# main.net
KiCad netlist of a schematic drawn in Altium Designer
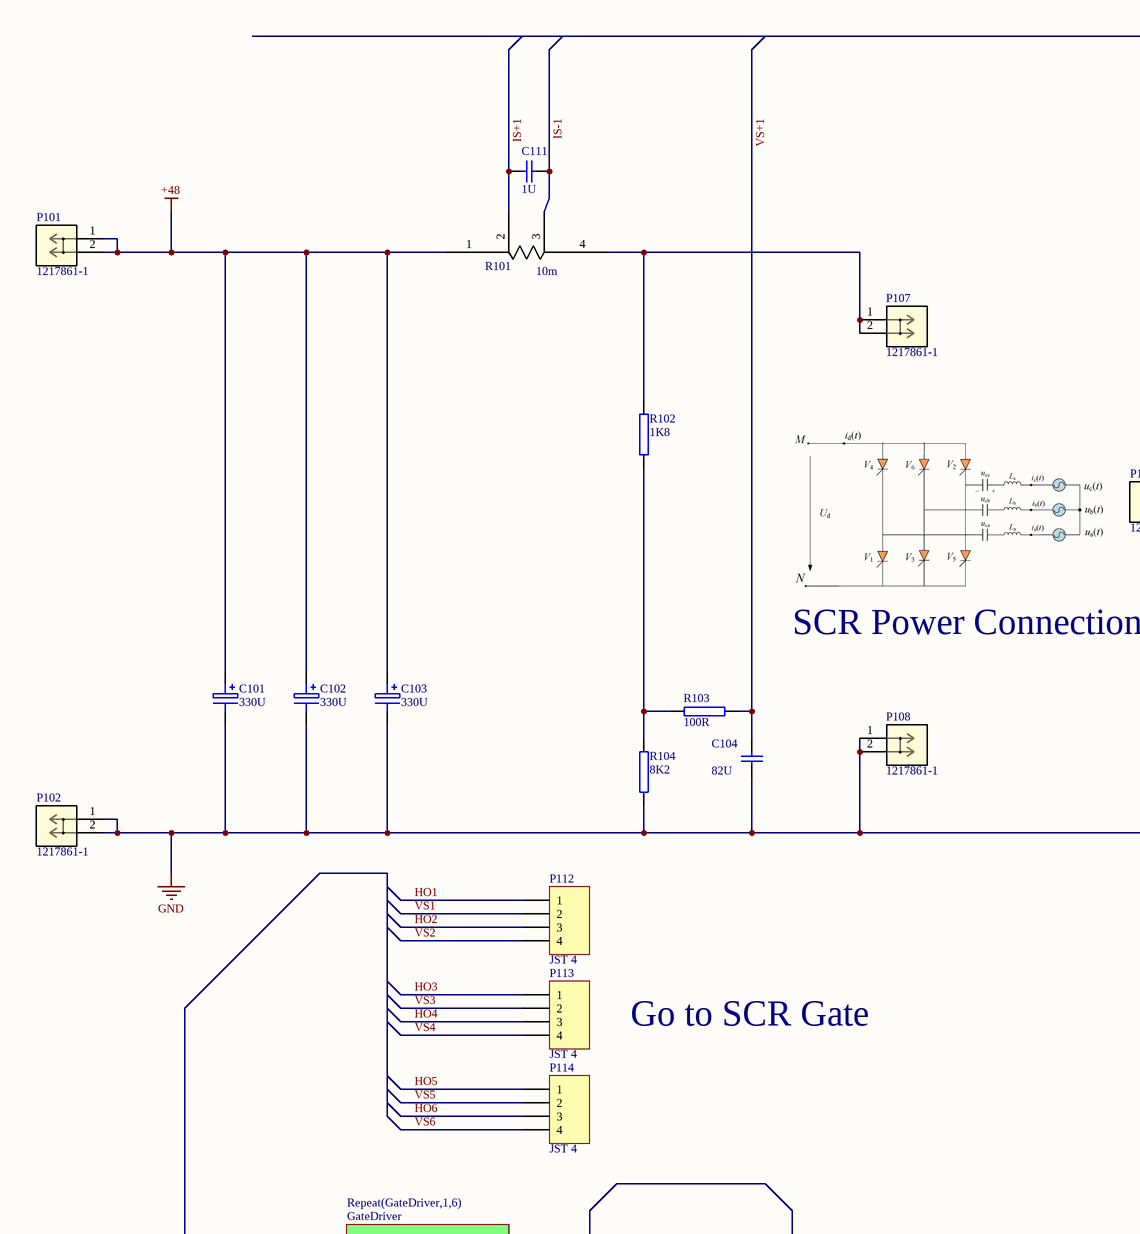
[diagram p0: main.SchDoc, top left]
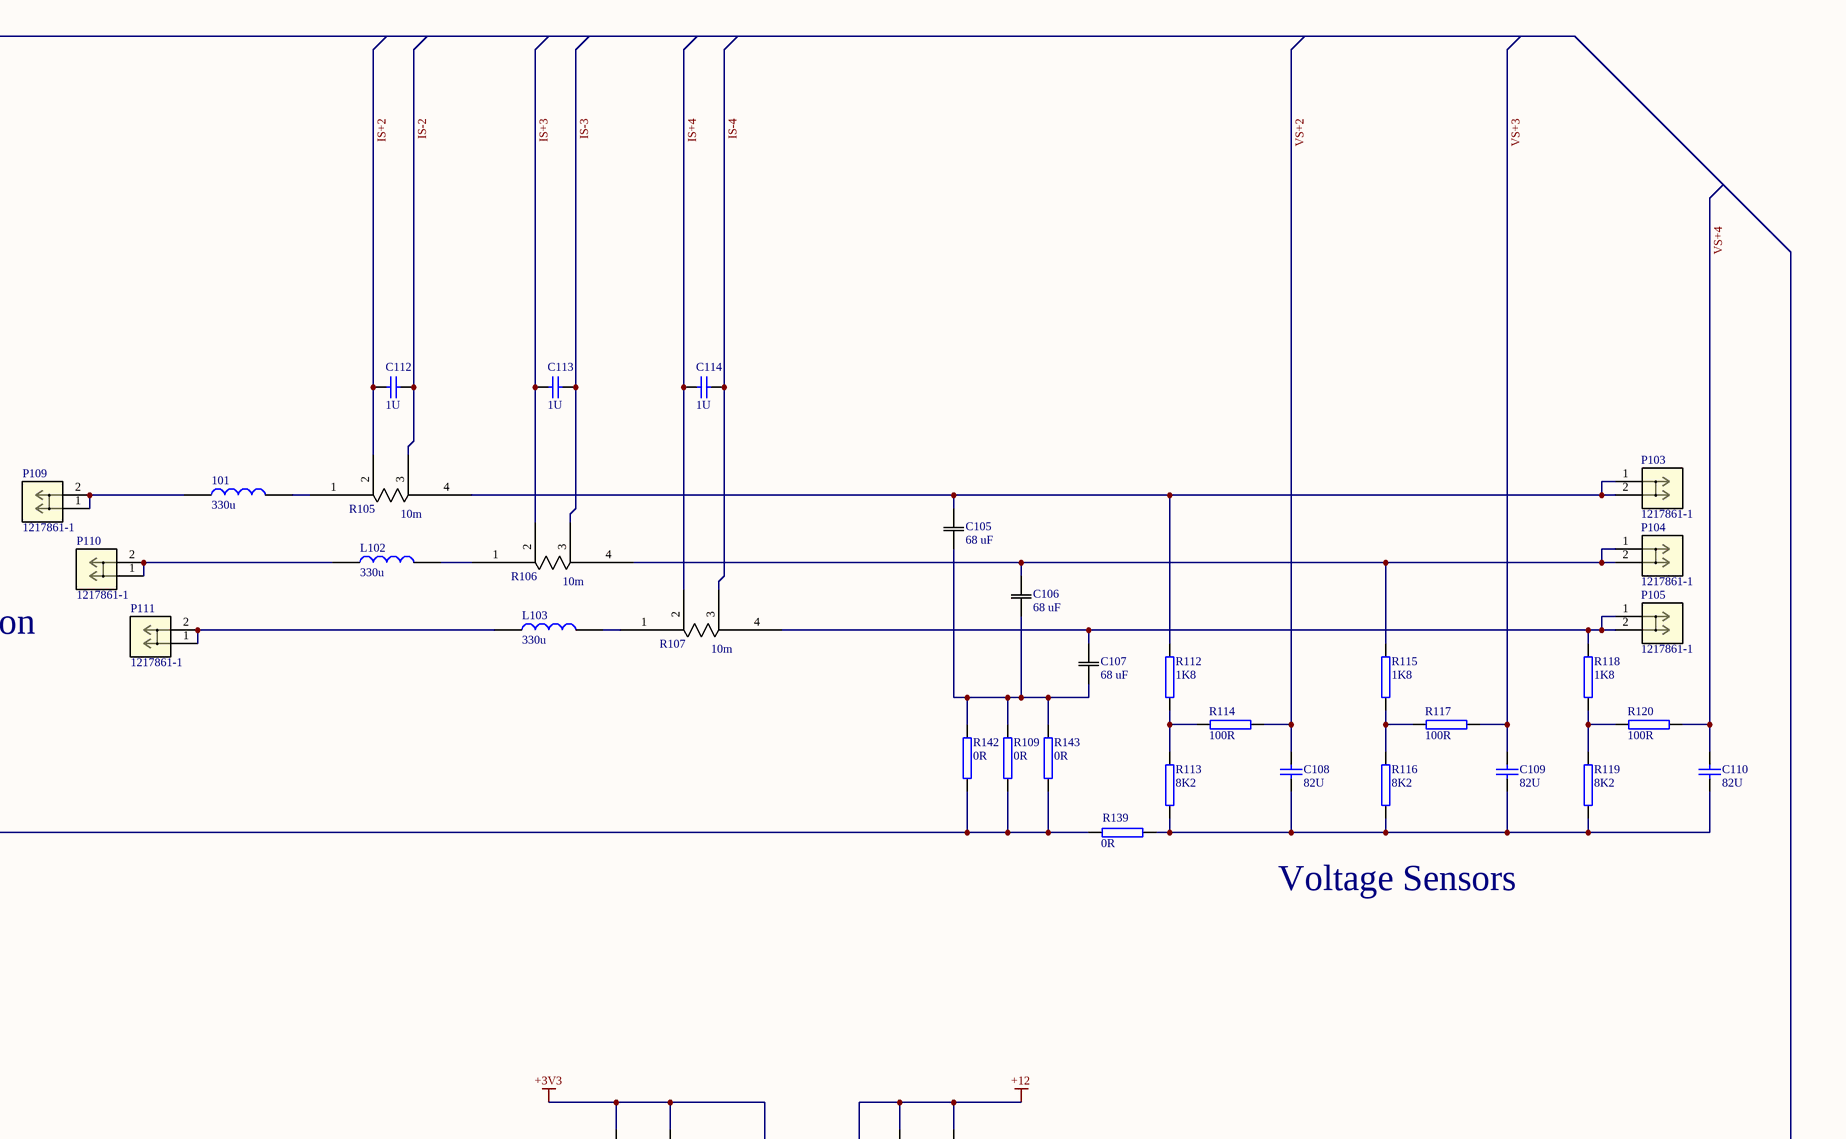
[diagram p1: main.SchDoc, top right]
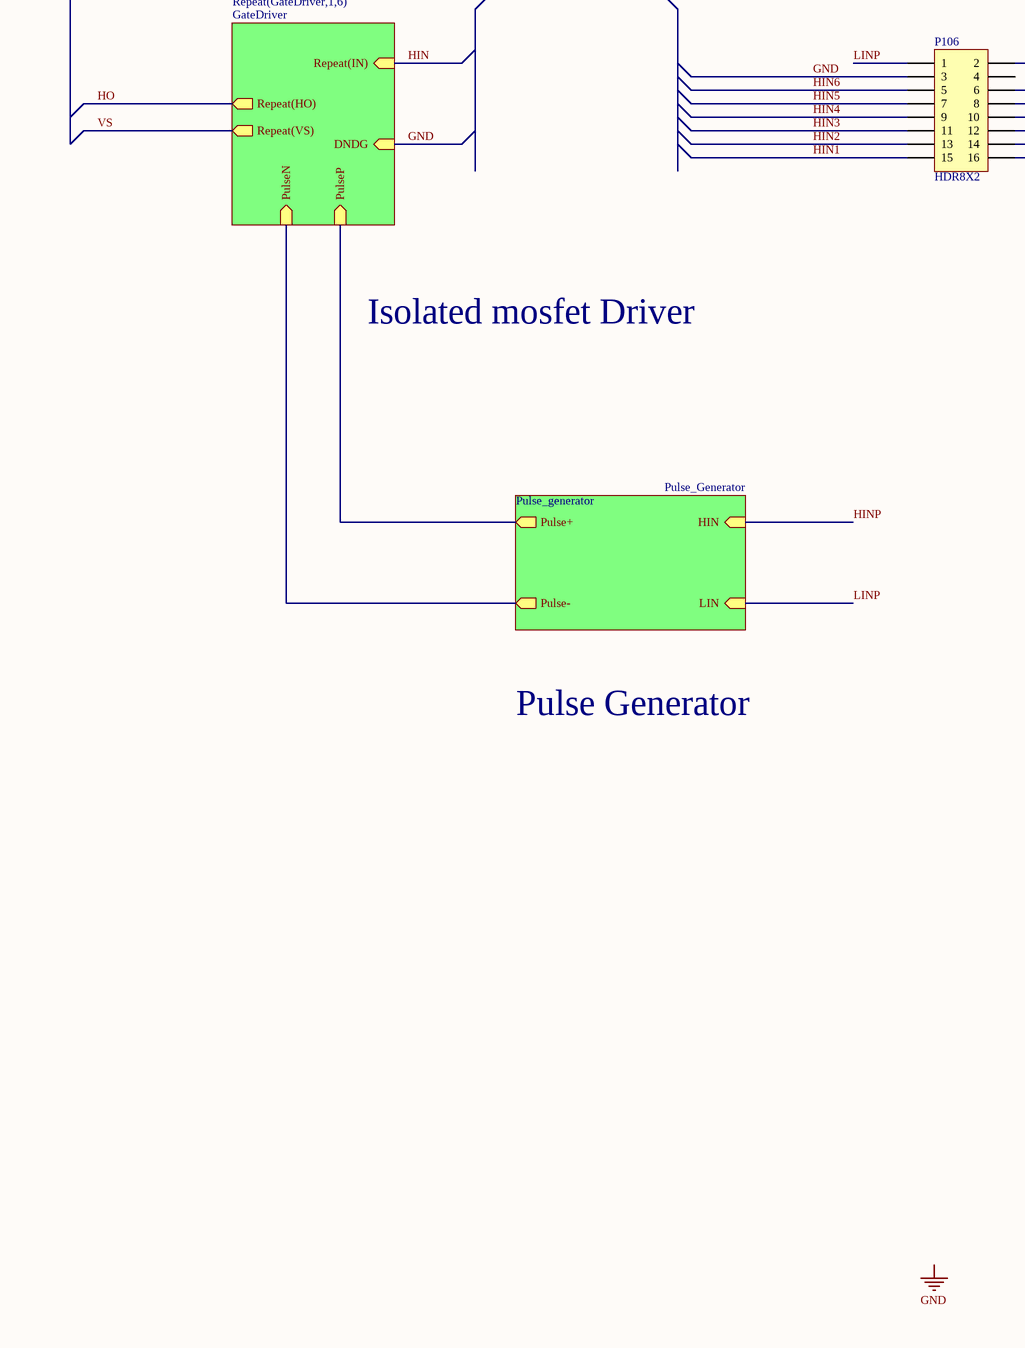
[diagram p2: main.SchDoc, bottom left]
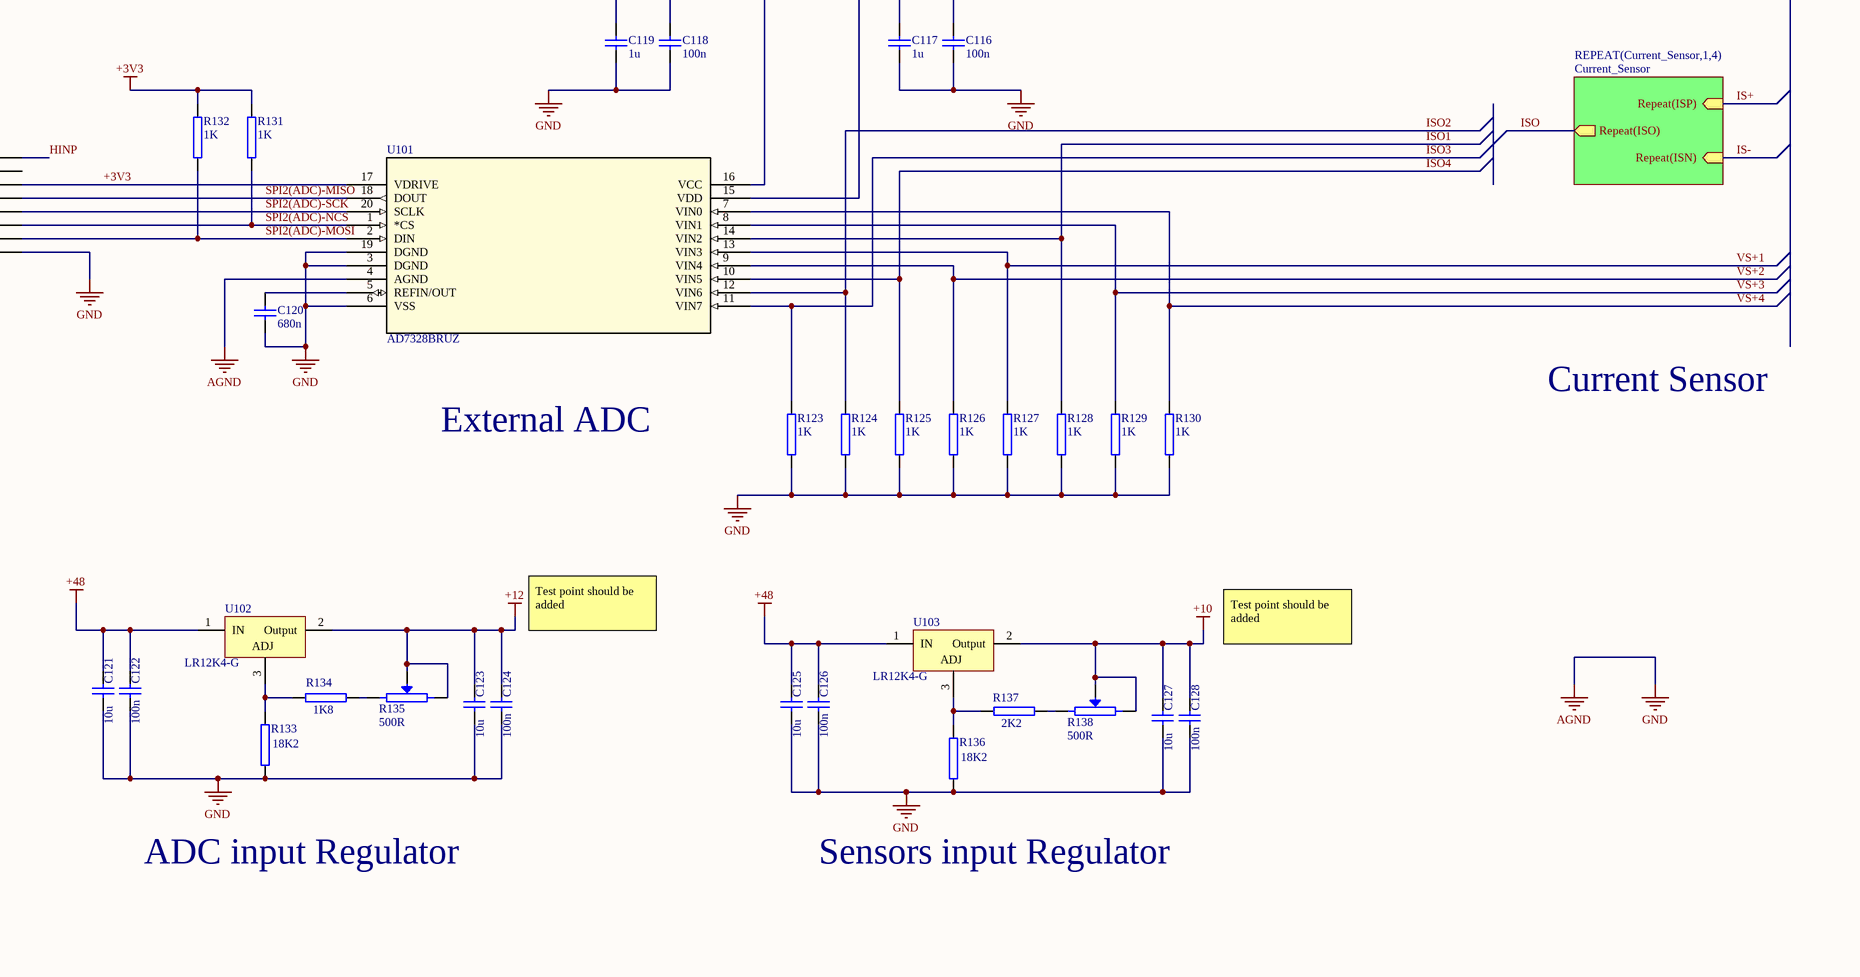
[diagram p3: main.SchDoc, bottom right]

(export (version "E")
  (design (tool "Eeschema 10.0.6"))
  (components
    (comp (ref "101")
      (value "330u")
      (footprint "1140-331K-RC")
      (libsource (lib "ENEL709_Schematic_Library") (part "1140-331K-RC"))
    )
    (comp (ref "C101")
      (value "330U")
      (footprint "CAPP300-600_AUT")
      (description "Polarized Aluminum Capacitor, Through Hole, Pitch 300mil, Body 600mil (Dia)")
      (libsource (lib "Resistors and Capacitors") (part "CAPP300-600"))
    )
    (comp (ref "C102")
      (value "330U")
      (footprint "CAPP300-600_AUT")
      (description "Polarized Aluminum Capacitor, Through Hole, Pitch 300mil, Body 600mil (Dia)")
      (libsource (lib "Resistors and Capacitors") (part "CAPP300-600"))
    )
    (comp (ref "C103")
      (value "330U")
      (footprint "CAPP300-600_AUT")
      (description "Polarized Aluminum Capacitor, Through Hole, Pitch 300mil, Body 600mil (Dia)")
      (libsource (lib "Resistors and Capacitors") (part "CAPP300-600"))
    )
    (comp (ref "C104")
      (value "82U")
      (footprint "CAP_1206")
      (description "Non Polarized Capacitor, SMD, 1206")
      (libsource (lib "Resistors and Capacitors") (part "CAPN 1206"))
    )
    (comp (ref "C105")
      (value "68 uF")
      (footprint "B32526R3686K000")
      (libsource (lib "ENEL709_Schematic_Library") (part "B32526R3686K000"))
    )
    (comp (ref "C106")
      (value "68 uF")
      (footprint "B32526R3686K000")
      (libsource (lib "ENEL709_Schematic_Library") (part "B32526R3686K000"))
    )
    (comp (ref "C107")
      (value "68 uF")
      (footprint "B32526R3686K000")
      (libsource (lib "ENEL709_Schematic_Library") (part "B32526R3686K000"))
    )
    (comp (ref "C108")
      (value "82U")
      (footprint "CAP_1206")
      (description "Non Polarized Capacitor, SMD, 1206")
      (libsource (lib "Resistors and Capacitors") (part "CAPN 1206"))
    )
    (comp (ref "C109")
      (value "82U")
      (footprint "CAP_1206")
      (description "Non Polarized Capacitor, SMD, 1206")
      (libsource (lib "Resistors and Capacitors") (part "CAPN 1206"))
    )
    (comp (ref "C110")
      (value "82U")
      (footprint "CAP_1206")
      (description "Non Polarized Capacitor, SMD, 1206")
      (libsource (lib "Resistors and Capacitors") (part "CAPN 1206"))
    )
    (comp (ref "C111")
      (value "1U")
      (footprint "CAP_1206")
      (description "Non Polarized Capacitor, SMD, 1206")
      (libsource (lib "Resistors and Capacitors") (part "CAPN 1206"))
    )
    (comp (ref "C112")
      (value "1U")
      (footprint "CAP_1206")
      (description "Non Polarized Capacitor, SMD, 1206")
      (libsource (lib "Resistors and Capacitors") (part "CAPN 1206"))
    )
    (comp (ref "C113")
      (value "1U")
      (footprint "CAP_1206")
      (description "Non Polarized Capacitor, SMD, 1206")
      (libsource (lib "Resistors and Capacitors") (part "CAPN 1206"))
    )
    (comp (ref "C114")
      (value "1U")
      (footprint "CAP_1206")
      (description "Non Polarized Capacitor, SMD, 1206")
      (libsource (lib "Resistors and Capacitors") (part "CAPN 1206"))
    )
    (comp (ref "C116")
      (value "100n")
      (footprint "CAP_1206")
      (description "Non Polarized Capacitor, SMD, 1206")
      (libsource (lib "Resistors and Capacitors") (part "CAPN 1206"))
    )
    (comp (ref "C117")
      (value "1u")
      (footprint "CAP_1206")
      (description "Non Polarized Capacitor, SMD, 1206")
      (libsource (lib "Resistors and Capacitors") (part "CAPN 1206"))
    )
    (comp (ref "C118")
      (value "100n")
      (footprint "CAP_1206")
      (description "Non Polarized Capacitor, SMD, 1206")
      (libsource (lib "Resistors and Capacitors") (part "CAPN 1206"))
    )
    (comp (ref "C119")
      (value "1u")
      (footprint "CAP_1206")
      (description "Non Polarized Capacitor, SMD, 1206")
      (libsource (lib "Resistors and Capacitors") (part "CAPN 1206"))
    )
    (comp (ref "C120")
      (value "680n")
      (footprint "CAP_1206")
      (description "Non Polarized Capacitor, SMD, 1206")
      (libsource (lib "Resistors and Capacitors") (part "CAPN 1206"))
    )
    (comp (ref "C121")
      (value "10u")
      (footprint "CAP_1206")
      (description "Non Polarized Capacitor, SMD, 1206")
      (libsource (lib "Resistors and Capacitors") (part "CAPN 1206"))
    )
    (comp (ref "C122")
      (value "100n")
      (footprint "CAP_1206")
      (description "Non Polarized Capacitor, SMD, 1206")
      (libsource (lib "Resistors and Capacitors") (part "CAPN 1206"))
    )
    (comp (ref "C123")
      (value "10u")
      (footprint "CAP_1206")
      (description "Non Polarized Capacitor, SMD, 1206")
      (libsource (lib "Resistors and Capacitors") (part "CAPN 1206"))
    )
    (comp (ref "C124")
      (value "100n")
      (footprint "CAP_1206")
      (description "Non Polarized Capacitor, SMD, 1206")
      (libsource (lib "Resistors and Capacitors") (part "CAPN 1206"))
    )
    (comp (ref "C125")
      (value "10u")
      (footprint "CAP_1206")
      (description "Non Polarized Capacitor, SMD, 1206")
      (libsource (lib "Resistors and Capacitors") (part "CAPN 1206"))
    )
    (comp (ref "C126")
      (value "100n")
      (footprint "CAP_1206")
      (description "Non Polarized Capacitor, SMD, 1206")
      (libsource (lib "Resistors and Capacitors") (part "CAPN 1206"))
    )
    (comp (ref "C127")
      (value "10u")
      (footprint "CAP_1206")
      (description "Non Polarized Capacitor, SMD, 1206")
      (libsource (lib "Resistors and Capacitors") (part "CAPN 1206"))
    )
    (comp (ref "C128")
      (value "100n")
      (footprint "CAP_1206")
      (description "Non Polarized Capacitor, SMD, 1206")
      (libsource (lib "Resistors and Capacitors") (part "CAPN 1206"))
    )
    (comp (ref "L102")
      (value "330u")
      (footprint "1140-331K-RC")
      (libsource (lib "ENEL709_Schematic_Library") (part "1140-331K-RC"))
    )
    (comp (ref "L103")
      (value "330u")
      (footprint "1140-331K-RC")
      (libsource (lib "ENEL709_Schematic_Library") (part "1140-331K-RC"))
    )
    (comp (ref "P101")
      (value "1217861-1")
      (footprint "CONN_1217861-1_TEC")
      (libsource (lib "") (part "1217861-1_2"))
    )
    (comp (ref "P102")
      (value "1217861-1")
      (footprint "CONN_1217861-1_TEC")
      (libsource (lib "") (part "1217861-1_2"))
    )
    (comp (ref "P103")
      (value "1217861-1")
      (footprint "CONN_1217861-1_TEC")
      (libsource (lib "Schlib") (part "1217861-1"))
    )
    (comp (ref "P104")
      (value "1217861-1")
      (footprint "CONN_1217861-1_TEC")
      (libsource (lib "Schlib") (part "1217861-1"))
    )
    (comp (ref "P105")
      (value "1217861-1")
      (footprint "CONN_1217861-1_TEC")
      (libsource (lib "Schlib") (part "1217861-1"))
    )
    (comp (ref "P106")
      (value "HDR8X2")
      (footprint "HDR2X8_AUT")
      (description "Header, 8-Pin, Dual row, 2.54mm Pitch, Straight")
      (libsource (lib "Connectors") (part "HDR8X2"))
    )
    (comp (ref "P107")
      (value "1217861-1")
      (footprint "CONN_1217861-1_TEC")
      (libsource (lib "Schlib") (part "1217861-1"))
    )
    (comp (ref "P108")
      (value "1217861-1")
      (footprint "CONN_1217861-1_TEC")
      (libsource (lib "Schlib") (part "1217861-1"))
    )
    (comp (ref "P109")
      (value "1217861-1")
      (footprint "CONN_1217861-1_TEC")
      (libsource (lib "") (part "1217861-1_1"))
    )
    (comp (ref "P110")
      (value "1217861-1")
      (footprint "CONN_1217861-1_TEC")
      (libsource (lib "") (part "1217861-1_1"))
    )
    (comp (ref "P111")
      (value "1217861-1")
      (footprint "CONN_1217861-1_TEC")
      (libsource (lib "") (part "1217861-1_1"))
    )
    (comp (ref "P112")
      (value "JST 4")
      (footprint "PA-4")
      (description "JST PA Header, 4-Pin, Pitch 2mm")
      (libsource (lib "Connectors") (part "JST PA Header 4"))
    )
    (comp (ref "P113")
      (value "JST 4")
      (footprint "PA-4")
      (description "JST PA Header, 4-Pin, Pitch 2mm")
      (libsource (lib "Connectors") (part "JST PA Header 4"))
    )
    (comp (ref "P114")
      (value "JST 4")
      (footprint "PA-4")
      (description "JST PA Header, 4-Pin, Pitch 2mm")
      (libsource (lib "Connectors") (part "JST PA Header 4"))
    )
    (comp (ref "R101")
      (value "10m")
      (footprint "WSL3673R_002-01")
      (description "Current Shunt \r\nKelvin 4W 0.002- 0.01")
      (libsource (lib "Projects_2025") (part "WSL3673R-01"))
    )
    (comp (ref "R102")
      (value "1K8")
      (footprint "RES_1206")
      (description "Resistor, SMD, 1206")
      (libsource (lib "Resistors and Capacitors") (part "Resistor 1206"))
    )
    (comp (ref "R103")
      (value "100R")
      (footprint "RES_1206")
      (description "Resistor, SMD, 1206")
      (libsource (lib "Resistors and Capacitors") (part "Resistor 1206"))
    )
    (comp (ref "R104")
      (value "8K2")
      (footprint "RES_1206")
      (description "Resistor, SMD, 1206")
      (libsource (lib "Resistors and Capacitors") (part "Resistor 1206"))
    )
    (comp (ref "R105")
      (value "10m")
      (footprint "WSL3673R_002-01")
      (description "Current Shunt \r\nKelvin 4W 0.002- 0.01")
      (libsource (lib "Projects_2025") (part "WSL3673R-01"))
    )
    (comp (ref "R106")
      (value "10m")
      (footprint "WSL3673R_002-01")
      (description "Current Shunt \r\nKelvin 4W 0.002- 0.01")
      (libsource (lib "Projects_2025") (part "WSL3673R-01"))
    )
    (comp (ref "R107")
      (value "10m")
      (footprint "WSL3673R_002-01")
      (description "Current Shunt \r\nKelvin 4W 0.002- 0.01")
      (libsource (lib "Projects_2025") (part "WSL3673R-01"))
    )
    (comp (ref "R109")
      (value "0R")
      (footprint "RES_1206")
      (description "Resistor, SMD, 1206")
      (libsource (lib "Resistors and Capacitors") (part "Resistor 1206"))
    )
    (comp (ref "R112")
      (value "1K8")
      (footprint "RES_1206")
      (description "Resistor, SMD, 1206")
      (libsource (lib "Resistors and Capacitors") (part "Resistor 1206"))
    )
    (comp (ref "R113")
      (value "8K2")
      (footprint "RES_1206")
      (description "Resistor, SMD, 1206")
      (libsource (lib "Resistors and Capacitors") (part "Resistor 1206"))
    )
    (comp (ref "R114")
      (value "100R")
      (footprint "RES_1206")
      (description "Resistor, SMD, 1206")
      (libsource (lib "Resistors and Capacitors") (part "Resistor 1206"))
    )
    (comp (ref "R115")
      (value "1K8")
      (footprint "RES_1206")
      (description "Resistor, SMD, 1206")
      (libsource (lib "Resistors and Capacitors") (part "Resistor 1206"))
    )
    (comp (ref "R116")
      (value "8K2")
      (footprint "RES_1206")
      (description "Resistor, SMD, 1206")
      (libsource (lib "Resistors and Capacitors") (part "Resistor 1206"))
    )
    (comp (ref "R117")
      (value "100R")
      (footprint "RES_1206")
      (description "Resistor, SMD, 1206")
      (libsource (lib "Resistors and Capacitors") (part "Resistor 1206"))
    )
    (comp (ref "R118")
      (value "1K8")
      (footprint "RES_1206")
      (description "Resistor, SMD, 1206")
      (libsource (lib "Resistors and Capacitors") (part "Resistor 1206"))
    )
    (comp (ref "R119")
      (value "8K2")
      (footprint "RES_1206")
      (description "Resistor, SMD, 1206")
      (libsource (lib "Resistors and Capacitors") (part "Resistor 1206"))
    )
    (comp (ref "R120")
      (value "100R")
      (footprint "RES_1206")
      (description "Resistor, SMD, 1206")
      (libsource (lib "Resistors and Capacitors") (part "Resistor 1206"))
    )
    (comp (ref "R123")
      (value "1K")
      (footprint "RES_1206")
      (description "Resistor, SMD, 1206")
      (libsource (lib "Resistors and Capacitors") (part "Resistor 1206"))
    )
    (comp (ref "R124")
      (value "1K")
      (footprint "RES_1206")
      (description "Resistor, SMD, 1206")
      (libsource (lib "Resistors and Capacitors") (part "Resistor 1206"))
    )
    (comp (ref "R125")
      (value "1K")
      (footprint "RES_1206")
      (description "Resistor, SMD, 1206")
      (libsource (lib "Resistors and Capacitors") (part "Resistor 1206"))
    )
    (comp (ref "R126")
      (value "1K")
      (footprint "RES_1206")
      (description "Resistor, SMD, 1206")
      (libsource (lib "Resistors and Capacitors") (part "Resistor 1206"))
    )
    (comp (ref "R127")
      (value "1K")
      (footprint "RES_1206")
      (description "Resistor, SMD, 1206")
      (libsource (lib "Resistors and Capacitors") (part "Resistor 1206"))
    )
    (comp (ref "R128")
      (value "1K")
      (footprint "RES_1206")
      (description "Resistor, SMD, 1206")
      (libsource (lib "Resistors and Capacitors") (part "Resistor 1206"))
    )
    (comp (ref "R129")
      (value "1K")
      (footprint "RES_1206")
      (description "Resistor, SMD, 1206")
      (libsource (lib "Resistors and Capacitors") (part "Resistor 1206"))
    )
    (comp (ref "R130")
      (value "1K")
      (footprint "RES_1206")
      (description "Resistor, SMD, 1206")
      (libsource (lib "Resistors and Capacitors") (part "Resistor 1206"))
    )
    (comp (ref "R131")
      (value "1K")
      (footprint "RES_1206")
      (description "Resistor, SMD, 1206")
      (libsource (lib "Resistors and Capacitors") (part "Resistor 1206"))
    )
    (comp (ref "R132")
      (value "1K")
      (footprint "RES_1206")
      (description "Resistor, SMD, 1206")
      (libsource (lib "Resistors and Capacitors") (part "Resistor 1206"))
    )
    (comp (ref "R133")
      (value "18K2")
      (footprint "RES_1206")
      (description "Resistor, SMD, 1206")
      (libsource (lib "Resistors and Capacitors") (part "Resistor 1206"))
    )
    (comp (ref "R134")
      (value "1K8")
      (footprint "RES_1206")
      (description "Resistor, SMD, 1206")
      (libsource (lib "Resistors and Capacitors") (part "Resistor 1206"))
    )
    (comp (ref "R135")
      (value "500R")
      (footprint "3296W")
      (libsource (lib "Potentiometers") (part "3296W-1-104LF"))
    )
    (comp (ref "R136")
      (value "18K2")
      (footprint "RES_1206")
      (description "Resistor, SMD, 1206")
      (libsource (lib "Resistors and Capacitors") (part "Resistor 1206"))
    )
    (comp (ref "R137")
      (value "2K2")
      (footprint "RES_1206")
      (description "Resistor, SMD, 1206")
      (libsource (lib "Resistors and Capacitors") (part "Resistor 1206"))
    )
    (comp (ref "R138")
      (value "500R")
      (footprint "3296W")
      (libsource (lib "Potentiometers") (part "3296W-1-104LF"))
    )
    (comp (ref "R139")
      (value "0R")
      (footprint "RES_1206")
      (description "Resistor, SMD, 1206")
      (libsource (lib "Resistors and Capacitors") (part "Resistor 1206"))
    )
    (comp (ref "R142")
      (value "0R")
      (footprint "RES_1206")
      (description "Resistor, SMD, 1206")
      (libsource (lib "Resistors and Capacitors") (part "Resistor 1206"))
    )
    (comp (ref "R143")
      (value "0R")
      (footprint "RES_1206")
      (description "Resistor, SMD, 1206")
      (libsource (lib "Resistors and Capacitors") (part "Resistor 1206"))
    )
    (comp (ref "U101")
      (value "AD7328BRUZ")
      (footprint "TSSOP20_44")
      (description "ADC 12 Bit\r\nPackage TSSOP20")
      (libsource (lib "Projects_2025") (part "AD7328BRUZ"))
    )
    (comp (ref "U102")
      (value "LR12K4-G")
      (footprint "D PAK (TO-252-3)")
      (description "Adj Positive Regulator \r\nLinear. 12V dropout V. \r\n2W")
      (libsource (lib "Projects_2025") (part "LR12K4-G"))
    )
    (comp (ref "U103")
      (value "LR12K4-G")
      (footprint "D PAK (TO-252-3)")
      (description "Adj Positive Regulator \r\nLinear. 12V dropout V. \r\n2W")
      (libsource (lib "Projects_2025") (part "LR12K4-G"))
    )
  )
  (nets
    (net (code "1") (name "+3V3") (class "Default")
      (node (ref "C118") (pin "2") (pinfunction "2_2") (pintype "passive"))
      (node (ref "C119") (pin "2") (pinfunction "2_2") (pintype "passive"))
      (node (ref "P106") (pin "6") (pinfunction "6_6") (pintype "passive"))
      (node (ref "R131") (pin "2") (pinfunction "2_2") (pintype "passive"))
      (node (ref "R132") (pin "2") (pinfunction "2_2") (pintype "passive"))
      (node (ref "U101") (pin "16") (pinfunction "VCC_16") (pintype "power_in"))
      (node (ref "U101") (pin "17") (pinfunction "VDRIVE_17") (pintype "power_in"))
    )
    (net (code "2") (name "+10") (class "Default")
      (node (ref "C127") (pin "2") (pinfunction "2_2") (pintype "passive"))
      (node (ref "C128") (pin "2") (pinfunction "2_2") (pintype "passive"))
      (node (ref "R138") (pin "2") (pinfunction "BOT_2") (pintype "passive"))
      (node (ref "R138") (pin "W") (pinfunction "TAP_W") (pintype "passive"))
      (node (ref "U103") (pin "2") (pinfunction "Output_2") (pintype "power_in"))
    )
    (net (code "3") (name "+12") (class "Default")
      (node (ref "C116") (pin "2") (pinfunction "2_2") (pintype "passive"))
      (node (ref "C117") (pin "2") (pinfunction "2_2") (pintype "passive"))
      (node (ref "C123") (pin "2") (pinfunction "2_2") (pintype "passive"))
      (node (ref "C124") (pin "2") (pinfunction "2_2") (pintype "passive"))
      (node (ref "R135") (pin "2") (pinfunction "BOT_2") (pintype "passive"))
      (node (ref "R135") (pin "W") (pinfunction "TAP_W") (pintype "passive"))
      (node (ref "U101") (pin "15") (pinfunction "VDD_15") (pintype "power_in"))
      (node (ref "U102") (pin "2") (pinfunction "Output_2") (pintype "power_in"))
    )
    (net (code "4") (name "+48") (class "Default")
      (node (ref "C101") (pin "1") (pinfunction "1_1") (pintype "passive"))
      (node (ref "C102") (pin "1") (pinfunction "1_1") (pintype "passive"))
      (node (ref "C103") (pin "1") (pinfunction "1_1") (pintype "passive"))
      (node (ref "C121") (pin "2") (pinfunction "2_2") (pintype "passive"))
      (node (ref "C122") (pin "2") (pinfunction "2_2") (pintype "passive"))
      (node (ref "C125") (pin "2") (pinfunction "2_2") (pintype "passive"))
      (node (ref "C126") (pin "2") (pinfunction "2_2") (pintype "passive"))
      (node (ref "P101") (pin "1") (pinfunction "1_1") (pintype "passive"))
      (node (ref "P101") (pin "2") (pinfunction "2_2") (pintype "passive"))
      (node (ref "R101") (pin "1") (pinfunction "1_1") (pintype "passive"))
      (node (ref "U102") (pin "1") (pinfunction "IN_1") (pintype "power_in"))
      (node (ref "U103") (pin "1") (pinfunction "IN_1") (pintype "power_in"))
    )
    (net (code "6") (name "/HIN1") (class "Default")
      (node (ref "P106") (pin "15") (pinfunction "15_15") (pintype "passive"))
    )
    (net (code "7") (name "/HIN2") (class "Default")
      (node (ref "P106") (pin "13") (pinfunction "13_13") (pintype "passive"))
    )
    (net (code "8") (name "/HIN3") (class "Default")
      (node (ref "P106") (pin "11") (pinfunction "11_11") (pintype "passive"))
    )
    (net (code "9") (name "/HIN4") (class "Default")
      (node (ref "P106") (pin "9") (pinfunction "9_9") (pintype "passive"))
    )
    (net (code "10") (name "/HIN5") (class "Default")
      (node (ref "P106") (pin "7") (pinfunction "7_7") (pintype "passive"))
    )
    (net (code "11") (name "/HIN6") (class "Default")
      (node (ref "P106") (pin "5") (pinfunction "5_5") (pintype "passive"))
    )
    (net (code "12") (name "/HINP") (class "Default")
      (node (ref "P106") (pin "2") (pinfunction "2_2") (pintype "passive"))
    )
    (net (code "14") (name "/HO1") (class "Default")
      (node (ref "P112") (pin "1") (pinfunction "1_1") (pintype "passive"))
    )
    (net (code "15") (name "/HO2") (class "Default")
      (node (ref "P112") (pin "3") (pinfunction "3_3") (pintype "passive"))
    )
    (net (code "16") (name "/HO3") (class "Default")
      (node (ref "P113") (pin "1") (pinfunction "1_1") (pintype "passive"))
    )
    (net (code "17") (name "/HO4") (class "Default")
      (node (ref "P113") (pin "3") (pinfunction "3_3") (pintype "passive"))
    )
    (net (code "18") (name "/HO5") (class "Default")
      (node (ref "P114") (pin "1") (pinfunction "1_1") (pintype "passive"))
    )
    (net (code "19") (name "/HO6") (class "Default")
      (node (ref "P114") (pin "3") (pinfunction "3_3") (pintype "passive"))
    )
    (net (code "21") (name "/IS+1") (class "Default")
      (node (ref "C111") (pin "2") (pinfunction "2_2") (pintype "passive"))
      (node (ref "R101") (pin "2") (pinfunction "2_2") (pintype "passive"))
    )
    (net (code "22") (name "/IS+2") (class "Default")
      (node (ref "C112") (pin "2") (pinfunction "2_2") (pintype "passive"))
      (node (ref "R105") (pin "2") (pinfunction "2_2") (pintype "passive"))
    )
    (net (code "23") (name "/IS+3") (class "Default")
      (node (ref "C113") (pin "2") (pinfunction "2_2") (pintype "passive"))
      (node (ref "R106") (pin "2") (pinfunction "2_2") (pintype "passive"))
    )
    (net (code "24") (name "/IS+4") (class "Default")
      (node (ref "C114") (pin "2") (pinfunction "2_2") (pintype "passive"))
      (node (ref "R107") (pin "2") (pinfunction "2_2") (pintype "passive"))
    )
    (net (code "26") (name "/IS-1") (class "Default")
      (node (ref "C111") (pin "1") (pinfunction "1_1") (pintype "passive"))
      (node (ref "R101") (pin "3") (pinfunction "3_3") (pintype "passive"))
    )
    (net (code "27") (name "/IS-2") (class "Default")
      (node (ref "C112") (pin "1") (pinfunction "1_1") (pintype "passive"))
      (node (ref "R105") (pin "3") (pinfunction "3_3") (pintype "passive"))
    )
    (net (code "28") (name "/IS-3") (class "Default")
      (node (ref "C113") (pin "1") (pinfunction "1_1") (pintype "passive"))
      (node (ref "R106") (pin "3") (pinfunction "3_3") (pintype "passive"))
    )
    (net (code "29") (name "/IS-4") (class "Default")
      (node (ref "C114") (pin "1") (pinfunction "1_1") (pintype "passive"))
      (node (ref "R107") (pin "3") (pinfunction "3_3") (pintype "passive"))
    )
    (net (code "31") (name "/ISO1") (class "Default")
      (node (ref "R128") (pin "2") (pinfunction "2_2") (pintype "passive"))
      (node (ref "U101") (pin "14") (pinfunction "VIN2_14") (pintype "input"))
    )
    (net (code "32") (name "/ISO2") (class "Default")
      (node (ref "R124") (pin "2") (pinfunction "2_2") (pintype "passive"))
      (node (ref "U101") (pin "12") (pinfunction "VIN6_12") (pintype "input"))
    )
    (net (code "33") (name "/ISO3") (class "Default")
      (node (ref "R123") (pin "2") (pinfunction "2_2") (pintype "passive"))
      (node (ref "U101") (pin "11") (pinfunction "VIN7_11") (pintype "input"))
    )
    (net (code "34") (name "/ISO4") (class "Default")
      (node (ref "R125") (pin "2") (pinfunction "2_2") (pintype "passive"))
      (node (ref "U101") (pin "10") (pinfunction "VIN5_10") (pintype "input"))
    )
    (net (code "35") (name "/LINP") (class "Default")
      (node (ref "P106") (pin "1") (pinfunction "1_1") (pintype "passive"))
    )
    (net (code "38") (name "/SPI2(ADC)-MISO") (class "Default")
      (node (ref "P106") (pin "8") (pinfunction "8_8") (pintype "passive"))
      (node (ref "U101") (pin "18") (pinfunction "DOUT_18") (pintype "output"))
    )
    (net (code "39") (name "/SPI2(ADC)-MOSI") (class "Default")
      (node (ref "P106") (pin "14") (pinfunction "14_14") (pintype "passive"))
      (node (ref "R132") (pin "1") (pinfunction "1_1") (pintype "passive"))
      (node (ref "U101") (pin "2") (pinfunction "DIN_2") (pintype "input"))
    )
    (net (code "40") (name "/SPI2(ADC)-NCS") (class "Default")
      (node (ref "P106") (pin "12") (pinfunction "12_12") (pintype "passive"))
      (node (ref "R131") (pin "1") (pinfunction "1_1") (pintype "passive"))
      (node (ref "U101") (pin "1") (pinfunction "*CS_1") (pintype "input"))
    )
    (net (code "41") (name "/SPI2(ADC)-SCK") (class "Default")
      (node (ref "P106") (pin "10") (pinfunction "10_10") (pintype "passive"))
      (node (ref "U101") (pin "20") (pinfunction "SCLK_20") (pintype "input"))
    )
    (net (code "43") (name "/VS+1") (class "Default")
      (node (ref "C104") (pin "2") (pinfunction "2_2") (pintype "passive"))
      (node (ref "R103") (pin "1") (pinfunction "1_1") (pintype "passive"))
      (node (ref "R127") (pin "2") (pinfunction "2_2") (pintype "passive"))
      (node (ref "U101") (pin "13") (pinfunction "VIN3_13") (pintype "input"))
    )
    (net (code "44") (name "/VS+2") (class "Default")
      (node (ref "C108") (pin "2") (pinfunction "2_2") (pintype "passive"))
      (node (ref "R114") (pin "1") (pinfunction "1_1") (pintype "passive"))
      (node (ref "R126") (pin "2") (pinfunction "2_2") (pintype "passive"))
      (node (ref "U101") (pin "9") (pinfunction "VIN4_9") (pintype "input"))
    )
    (net (code "45") (name "/VS+3") (class "Default")
      (node (ref "C109") (pin "2") (pinfunction "2_2") (pintype "passive"))
      (node (ref "R117") (pin "1") (pinfunction "1_1") (pintype "passive"))
      (node (ref "R129") (pin "2") (pinfunction "2_2") (pintype "passive"))
      (node (ref "U101") (pin "8") (pinfunction "VIN1_8") (pintype "input"))
    )
    (net (code "46") (name "/VS+4") (class "Default")
      (node (ref "C110") (pin "2") (pinfunction "2_2") (pintype "passive"))
      (node (ref "R120") (pin "1") (pinfunction "1_1") (pintype "passive"))
      (node (ref "R130") (pin "2") (pinfunction "2_2") (pintype "passive"))
      (node (ref "U101") (pin "7") (pinfunction "VIN0_7") (pintype "input"))
    )
    (net (code "47") (name "/VS1") (class "Default")
      (node (ref "P112") (pin "2") (pinfunction "2_2") (pintype "passive"))
    )
    (net (code "48") (name "/VS2") (class "Default")
      (node (ref "P112") (pin "4") (pinfunction "4_4") (pintype "passive"))
    )
    (net (code "49") (name "/VS3") (class "Default")
      (node (ref "P113") (pin "2") (pinfunction "2_2") (pintype "passive"))
    )
    (net (code "50") (name "/VS4") (class "Default")
      (node (ref "P113") (pin "4") (pinfunction "4_4") (pintype "passive"))
    )
    (net (code "51") (name "/VS5") (class "Default")
      (node (ref "P114") (pin "2") (pinfunction "2_2") (pintype "passive"))
    )
    (net (code "52") (name "/VS6") (class "Default")
      (node (ref "P114") (pin "4") (pinfunction "4_4") (pintype "passive"))
    )
    (net (code "53") (name "AGND") (class "Default")
      (node (ref "C101") (pin "2") (pinfunction "2_2") (pintype "passive"))
      (node (ref "C102") (pin "2") (pinfunction "2_2") (pintype "passive"))
      (node (ref "C103") (pin "2") (pinfunction "2_2") (pintype "passive"))
      (node (ref "C104") (pin "1") (pinfunction "1_1") (pintype "passive"))
      (node (ref "C116") (pin "1") (pinfunction "1_1") (pintype "passive"))
      (node (ref "C117") (pin "1") (pinfunction "1_1") (pintype "passive"))
      (node (ref "C118") (pin "1") (pinfunction "1_1") (pintype "passive"))
      (node (ref "C119") (pin "1") (pinfunction "1_1") (pintype "passive"))
      (node (ref "C120") (pin "1") (pinfunction "1_1") (pintype "passive"))
      (node (ref "C121") (pin "1") (pinfunction "1_1") (pintype "passive"))
      (node (ref "C122") (pin "1") (pinfunction "1_1") (pintype "passive"))
      (node (ref "C123") (pin "1") (pinfunction "1_1") (pintype "passive"))
      (node (ref "C124") (pin "1") (pinfunction "1_1") (pintype "passive"))
      (node (ref "C125") (pin "1") (pinfunction "1_1") (pintype "passive"))
      (node (ref "C126") (pin "1") (pinfunction "1_1") (pintype "passive"))
      (node (ref "C127") (pin "1") (pinfunction "1_1") (pintype "passive"))
      (node (ref "C128") (pin "1") (pinfunction "1_1") (pintype "passive"))
      (node (ref "P102") (pin "1") (pinfunction "1_1") (pintype "passive"))
      (node (ref "P102") (pin "2") (pinfunction "2_2") (pintype "passive"))
      (node (ref "P106") (pin "16") (pinfunction "16_16") (pintype "passive"))
      (node (ref "P106") (pin "3") (pinfunction "3_3") (pintype "passive"))
      (node (ref "P108") (pin "1") (pinfunction "1_1") (pintype "passive"))
      (node (ref "P108") (pin "2") (pinfunction "2_2") (pintype "passive"))
      (node (ref "R104") (pin "1") (pinfunction "1_1") (pintype "passive"))
      (node (ref "R109") (pin "2") (pinfunction "2_2") (pintype "passive"))
      (node (ref "R123") (pin "1") (pinfunction "1_1") (pintype "passive"))
      (node (ref "R124") (pin "1") (pinfunction "1_1") (pintype "passive"))
      (node (ref "R125") (pin "1") (pinfunction "1_1") (pintype "passive"))
      (node (ref "R126") (pin "1") (pinfunction "1_1") (pintype "passive"))
      (node (ref "R127") (pin "1") (pinfunction "1_1") (pintype "passive"))
      (node (ref "R128") (pin "1") (pinfunction "1_1") (pintype "passive"))
      (node (ref "R129") (pin "1") (pinfunction "1_1") (pintype "passive"))
      (node (ref "R130") (pin "1") (pinfunction "1_1") (pintype "passive"))
      (node (ref "R133") (pin "1") (pinfunction "1_1") (pintype "passive"))
      (node (ref "R136") (pin "1") (pinfunction "1_1") (pintype "passive"))
      (node (ref "R139") (pin "1") (pinfunction "1_1") (pintype "passive"))
      (node (ref "R142") (pin "1") (pinfunction "1_1") (pintype "passive"))
      (node (ref "R143") (pin "2") (pinfunction "2_2") (pintype "passive"))
      (node (ref "U101") (pin "19") (pinfunction "DGND_19") (pintype "power_in"))
      (node (ref "U101") (pin "3") (pinfunction "DGND_3") (pintype "power_in"))
      (node (ref "U101") (pin "4") (pinfunction "AGND_4") (pintype "power_in"))
      (node (ref "U101") (pin "6") (pinfunction "VSS_6") (pintype "power_in"))
    )
    (net (code "54") (name "Net-(101-Pad1)") (class "Default")
      (node (ref "101") (pin "1") (pinfunction "1_1") (pintype "passive"))
      (node (ref "P109") (pin "1") (pinfunction "1_1") (pintype "passive"))
      (node (ref "P109") (pin "2") (pinfunction "2_2") (pintype "passive"))
    )
    (net (code "55") (name "Net-(101-Pad2)") (class "Default")
      (node (ref "101") (pin "2") (pinfunction "2_2") (pintype "passive"))
      (node (ref "R105") (pin "1") (pinfunction "1_1") (pintype "passive"))
    )
    (net (code "56") (name "Net-(C105-Pad1)") (class "Default")
      (node (ref "C105") (pin "1") (pinfunction "1_1") (pintype "passive"))
      (node (ref "C106") (pin "1") (pinfunction "1_1") (pintype "passive"))
      (node (ref "C107") (pin "1") (pinfunction "1_1") (pintype "passive"))
      (node (ref "R109") (pin "1") (pinfunction "1_1") (pintype "passive"))
      (node (ref "R142") (pin "2") (pinfunction "2_2") (pintype "passive"))
      (node (ref "R143") (pin "1") (pinfunction "1_1") (pintype "passive"))
    )
    (net (code "57") (name "Net-(C105-Pad2)") (class "Default")
      (node (ref "C105") (pin "2") (pinfunction "2_2") (pintype "passive"))
      (node (ref "P103") (pin "1") (pinfunction "1_1") (pintype "passive"))
      (node (ref "P103") (pin "2") (pinfunction "2_2") (pintype "passive"))
      (node (ref "R105") (pin "4") (pinfunction "4_4") (pintype "passive"))
      (node (ref "R112") (pin "2") (pinfunction "2_2") (pintype "passive"))
    )
    (net (code "58") (name "Net-(C106-Pad2)") (class "Default")
      (node (ref "C106") (pin "2") (pinfunction "2_2") (pintype "passive"))
      (node (ref "P104") (pin "1") (pinfunction "1_1") (pintype "passive"))
      (node (ref "P104") (pin "2") (pinfunction "2_2") (pintype "passive"))
      (node (ref "R106") (pin "4") (pinfunction "4_4") (pintype "passive"))
      (node (ref "R115") (pin "2") (pinfunction "2_2") (pintype "passive"))
    )
    (net (code "59") (name "Net-(C107-Pad2)") (class "Default")
      (node (ref "C107") (pin "2") (pinfunction "2_2") (pintype "passive"))
      (node (ref "P105") (pin "1") (pinfunction "1_1") (pintype "passive"))
      (node (ref "P105") (pin "2") (pinfunction "2_2") (pintype "passive"))
      (node (ref "R107") (pin "4") (pinfunction "4_4") (pintype "passive"))
      (node (ref "R118") (pin "2") (pinfunction "2_2") (pintype "passive"))
    )
    (net (code "60") (name "Net-(C108-Pad1)") (class "Default")
      (node (ref "C108") (pin "1") (pinfunction "1_1") (pintype "passive"))
      (node (ref "C109") (pin "1") (pinfunction "1_1") (pintype "passive"))
      (node (ref "C110") (pin "1") (pinfunction "1_1") (pintype "passive"))
      (node (ref "R113") (pin "1") (pinfunction "1_1") (pintype "passive"))
      (node (ref "R116") (pin "1") (pinfunction "1_1") (pintype "passive"))
      (node (ref "R119") (pin "1") (pinfunction "1_1") (pintype "passive"))
      (node (ref "R139") (pin "2") (pinfunction "2_2") (pintype "passive"))
    )
    (net (code "61") (name "Net-(L102-Pad1)") (class "Default")
      (node (ref "L102") (pin "1") (pinfunction "1_1") (pintype "passive"))
      (node (ref "P110") (pin "1") (pinfunction "1_1") (pintype "passive"))
      (node (ref "P110") (pin "2") (pinfunction "2_2") (pintype "passive"))
    )
    (net (code "62") (name "Net-(L102-Pad2)") (class "Default")
      (node (ref "L102") (pin "2") (pinfunction "2_2") (pintype "passive"))
      (node (ref "R106") (pin "1") (pinfunction "1_1") (pintype "passive"))
    )
    (net (code "63") (name "Net-(L103-Pad1)") (class "Default")
      (node (ref "L103") (pin "1") (pinfunction "1_1") (pintype "passive"))
      (node (ref "P111") (pin "1") (pinfunction "1_1") (pintype "passive"))
      (node (ref "P111") (pin "2") (pinfunction "2_2") (pintype "passive"))
    )
    (net (code "64") (name "Net-(L103-Pad2)") (class "Default")
      (node (ref "L103") (pin "2") (pinfunction "2_2") (pintype "passive"))
      (node (ref "R107") (pin "1") (pinfunction "1_1") (pintype "passive"))
    )
    (net (code "65") (name "Net-(P107-Pad1)") (class "Default")
      (node (ref "P107") (pin "1") (pinfunction "1_1") (pintype "passive"))
      (node (ref "P107") (pin "2") (pinfunction "2_2") (pintype "passive"))
      (node (ref "R101") (pin "4") (pinfunction "4_4") (pintype "passive"))
      (node (ref "R102") (pin "2") (pinfunction "2_2") (pintype "passive"))
    )
    (net (code "66") (name "Net-(R102-Pad1)") (class "Default")
      (node (ref "R102") (pin "1") (pinfunction "1_1") (pintype "passive"))
      (node (ref "R103") (pin "2") (pinfunction "2_2") (pintype "passive"))
      (node (ref "R104") (pin "2") (pinfunction "2_2") (pintype "passive"))
    )
    (net (code "67") (name "Net-(R112-Pad1)") (class "Default")
      (node (ref "R112") (pin "1") (pinfunction "1_1") (pintype "passive"))
      (node (ref "R113") (pin "2") (pinfunction "2_2") (pintype "passive"))
      (node (ref "R114") (pin "2") (pinfunction "2_2") (pintype "passive"))
    )
    (net (code "68") (name "Net-(R115-Pad1)") (class "Default")
      (node (ref "R115") (pin "1") (pinfunction "1_1") (pintype "passive"))
      (node (ref "R116") (pin "2") (pinfunction "2_2") (pintype "passive"))
      (node (ref "R117") (pin "2") (pinfunction "2_2") (pintype "passive"))
    )
    (net (code "69") (name "Net-(R118-Pad1)") (class "Default")
      (node (ref "R118") (pin "1") (pinfunction "1_1") (pintype "passive"))
      (node (ref "R119") (pin "2") (pinfunction "2_2") (pintype "passive"))
      (node (ref "R120") (pin "2") (pinfunction "2_2") (pintype "passive"))
    )
    (net (code "70") (name "Net-(R135-TOP)") (class "Default")
      (node (ref "R134") (pin "1") (pinfunction "1_1") (pintype "passive"))
      (node (ref "R135") (pin "1") (pinfunction "TOP_1") (pintype "passive"))
    )
    (net (code "71") (name "Net-(R138-TOP)") (class "Default")
      (node (ref "R137") (pin "1") (pinfunction "1_1") (pintype "passive"))
      (node (ref "R138") (pin "1") (pinfunction "TOP_1") (pintype "passive"))
    )
    (net (code "72") (name "Net-(U101-REFIN{slash}OUT)") (class "Default")
      (node (ref "C120") (pin "2") (pinfunction "2_2") (pintype "passive"))
      (node (ref "U101") (pin "5") (pinfunction "REFIN/OUT_5") (pintype "bidirectional"))
    )
    (net (code "73") (name "Net-(U102-ADJ)") (class "Default")
      (node (ref "R133") (pin "2") (pinfunction "2_2") (pintype "passive"))
      (node (ref "R134") (pin "2") (pinfunction "2_2") (pintype "passive"))
      (node (ref "U102") (pin "3") (pinfunction "ADJ_3") (pintype "power_in"))
    )
    (net (code "74") (name "Net-(U103-ADJ)") (class "Default")
      (node (ref "R136") (pin "2") (pinfunction "2_2") (pintype "passive"))
      (node (ref "R137") (pin "2") (pinfunction "2_2") (pintype "passive"))
      (node (ref "U103") (pin "3") (pinfunction "ADJ_3") (pintype "power_in"))
    )
    (net (code "75") (name "unconnected-(P106-Pad4)") (class "Default")
      (node (ref "P106") (pin "4") (pinfunction "4_4") (pintype "passive"))
    )
  )
)
